# BreakoutBoard.net
KiCad netlist of a schematic drawn in EAGLE
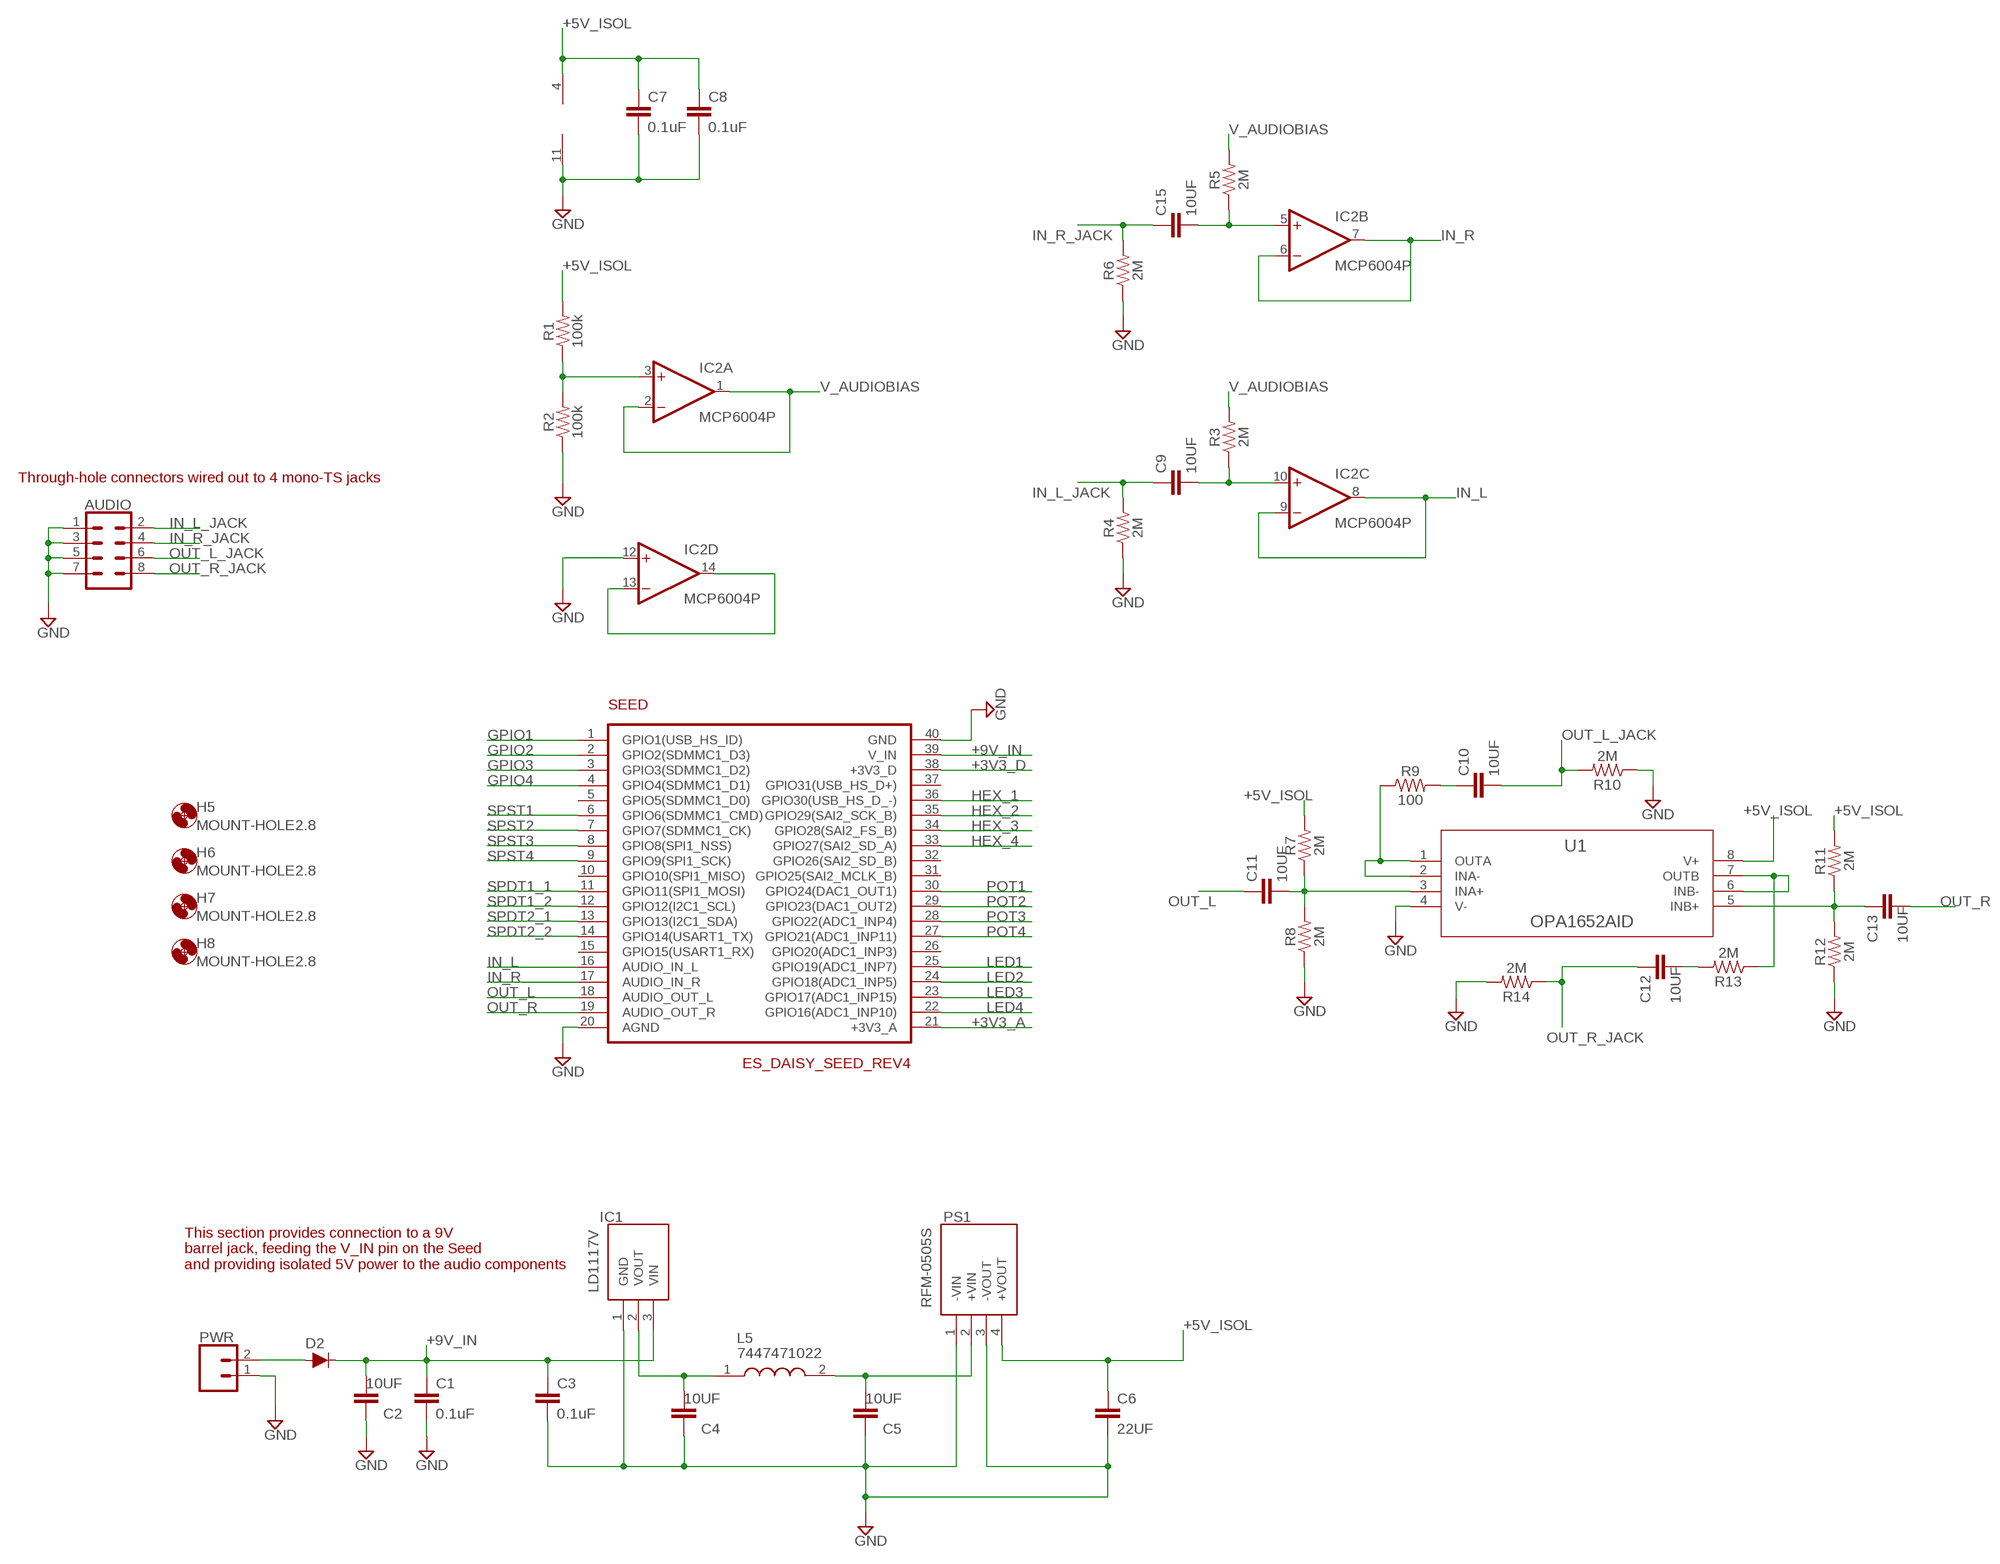
[diagram p0: schematic, sheet 1]
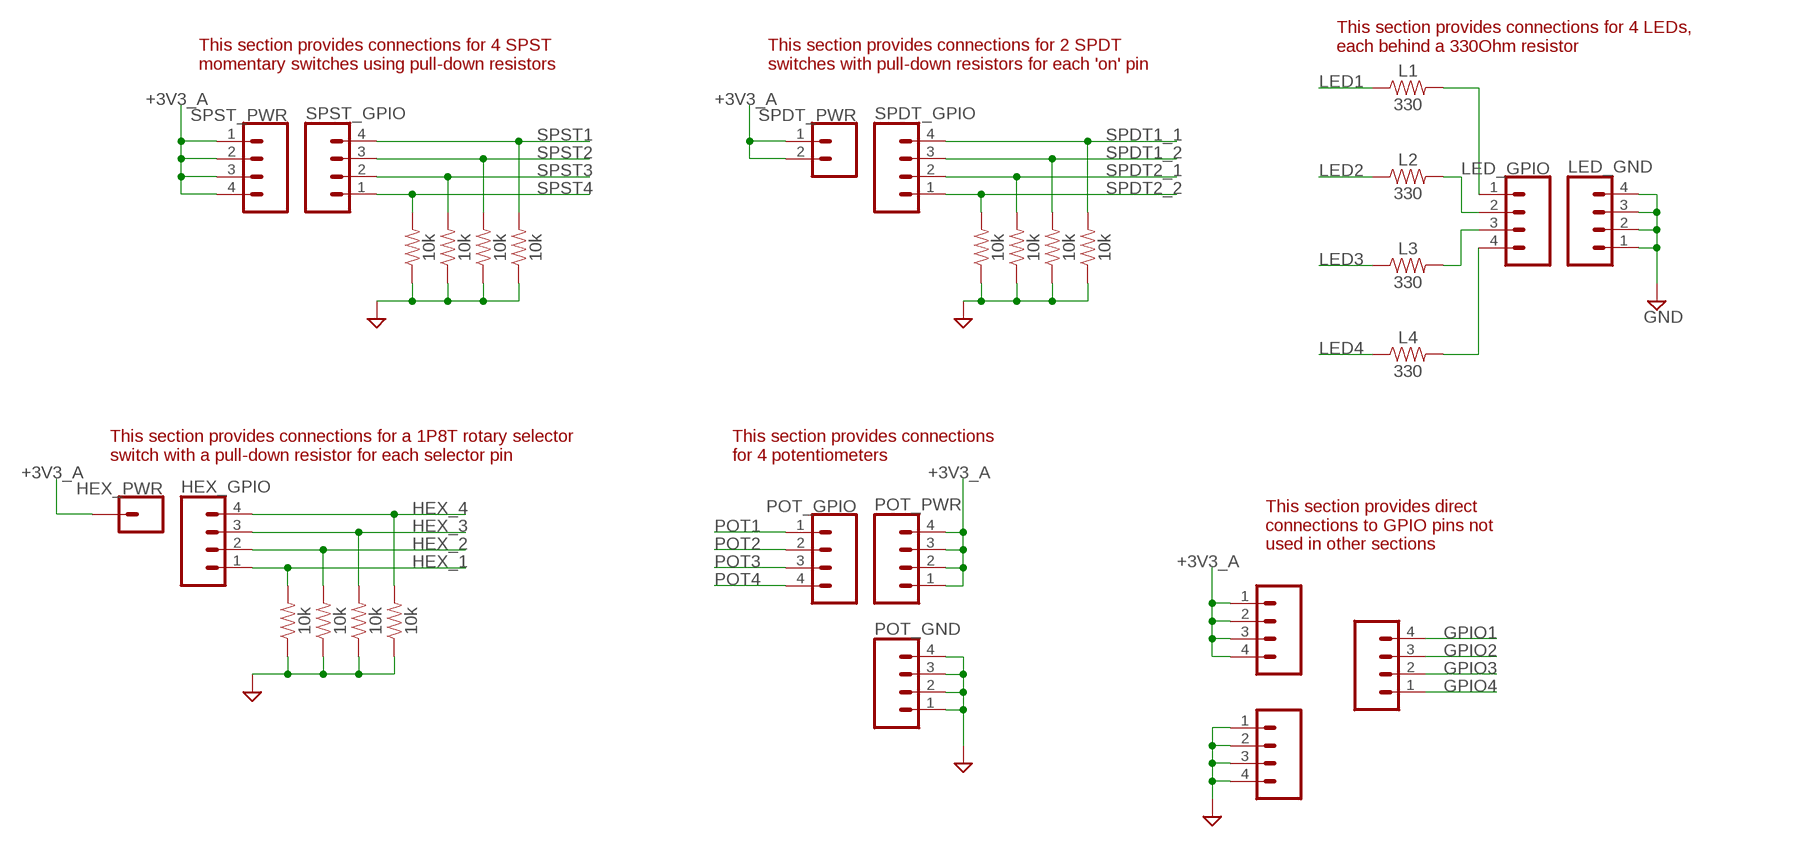
[diagram p1: schematic, sheet 2]

(export (version "E")
  (design (tool "Eeschema 10.0.6"))
  (components
    (comp (ref "EX_GND")
      (value "CONN_04")
      (footprint "eagle-import:1X04")
      (libsource (lib "eagle-import") (part "CONN_04"))
    )
    (comp (ref "EX_GPIOS")
      (value "CONN_04")
      (footprint "eagle-import:1X04")
      (libsource (lib "eagle-import") (part "CONN_04"))
    )
    (comp (ref "EX_PWR")
      (value "CONN_04")
      (footprint "eagle-import:1X04")
      (libsource (lib "eagle-import") (part "CONN_04"))
    )
    (comp (ref "HEX_GPIO")
      (value "CONN_04")
      (footprint "eagle-import:1X04")
      (libsource (lib "eagle-import") (part "CONN_04"))
    )
    (comp (ref "HEX_PWR")
      (value "CONN_01")
      (footprint "eagle-import:1X01")
      (libsource (lib "eagle-import") (part "CONN_01"))
    )
    (comp (ref "L1")
      (value "330")
      (footprint "eagle-import:AXIAL-0.3")
      (libsource (lib "eagle-import") (part "330OHM-HORIZ-1/10W-5%"))
    )
    (comp (ref "L2")
      (value "330")
      (footprint "eagle-import:AXIAL-0.3")
      (libsource (lib "eagle-import") (part "330OHM-HORIZ-1/10W-5%"))
    )
    (comp (ref "L3")
      (value "330")
      (footprint "eagle-import:AXIAL-0.3")
      (libsource (lib "eagle-import") (part "330OHM-HORIZ-1/10W-5%"))
    )
    (comp (ref "L4")
      (value "330")
      (footprint "eagle-import:AXIAL-0.3")
      (libsource (lib "eagle-import") (part "330OHM-HORIZ-1/10W-5%"))
    )
    (comp (ref "LED_GND")
      (value "CONN_04")
      (footprint "eagle-import:1X04")
      (libsource (lib "eagle-import") (part "CONN_04"))
    )
    (comp (ref "LED_GPIO")
      (value "CONN_04")
      (footprint "eagle-import:1X04")
      (libsource (lib "eagle-import") (part "CONN_04"))
    )
    (comp (ref "POT_GND")
      (value "CONN_04")
      (footprint "eagle-import:1X04")
      (libsource (lib "eagle-import") (part "CONN_04"))
    )
    (comp (ref "POT_GPIO")
      (value "CONN_04")
      (footprint "eagle-import:1X04")
      (libsource (lib "eagle-import") (part "CONN_04"))
    )
    (comp (ref "POT_PWR")
      (value "CONN_04")
      (footprint "eagle-import:1X04")
      (libsource (lib "eagle-import") (part "CONN_04"))
    )
    (comp (ref "R15")
      (value "10k")
      (footprint "eagle-import:AXIAL-0.3")
      (libsource (lib "eagle-import") (part "10KOHM-HORIZ-1/4W-5%"))
    )
    (comp (ref "R16")
      (value "10k")
      (footprint "eagle-import:AXIAL-0.3")
      (libsource (lib "eagle-import") (part "10KOHM-HORIZ-1/4W-5%"))
    )
    (comp (ref "R17")
      (value "10k")
      (footprint "eagle-import:AXIAL-0.3")
      (libsource (lib "eagle-import") (part "10KOHM-HORIZ-1/4W-5%"))
    )
    (comp (ref "R18")
      (value "10k")
      (footprint "eagle-import:AXIAL-0.3")
      (libsource (lib "eagle-import") (part "10KOHM-HORIZ-1/4W-5%"))
    )
    (comp (ref "R19")
      (value "10k")
      (footprint "eagle-import:AXIAL-0.3")
      (libsource (lib "eagle-import") (part "10KOHM-HORIZ-1/4W-5%"))
    )
    (comp (ref "R20")
      (value "10k")
      (footprint "eagle-import:AXIAL-0.3")
      (libsource (lib "eagle-import") (part "10KOHM-HORIZ-1/4W-5%"))
    )
    (comp (ref "R21")
      (value "10k")
      (footprint "eagle-import:AXIAL-0.3")
      (libsource (lib "eagle-import") (part "10KOHM-HORIZ-1/4W-5%"))
    )
    (comp (ref "R22")
      (value "10k")
      (footprint "eagle-import:AXIAL-0.3")
      (libsource (lib "eagle-import") (part "10KOHM-HORIZ-1/4W-5%"))
    )
    (comp (ref "R23")
      (value "10k")
      (footprint "eagle-import:AXIAL-0.3")
      (libsource (lib "eagle-import") (part "10KOHM-HORIZ-1/4W-5%"))
    )
    (comp (ref "R24")
      (value "10k")
      (footprint "eagle-import:AXIAL-0.3")
      (libsource (lib "eagle-import") (part "10KOHM-HORIZ-1/4W-5%"))
    )
    (comp (ref "R25")
      (value "10k")
      (footprint "eagle-import:AXIAL-0.3")
      (libsource (lib "eagle-import") (part "10KOHM-HORIZ-1/4W-5%"))
    )
    (comp (ref "R26")
      (value "10k")
      (footprint "eagle-import:AXIAL-0.3")
      (libsource (lib "eagle-import") (part "10KOHM-HORIZ-1/4W-5%"))
    )
    (comp (ref "SPDT_GPIO")
      (value "CONN_04")
      (footprint "eagle-import:1X04")
      (libsource (lib "eagle-import") (part "CONN_04"))
    )
    (comp (ref "SPDT_PWR")
      (value "CONN_02")
      (footprint "eagle-import:1X02")
      (libsource (lib "eagle-import") (part "CONN_02"))
    )
    (comp (ref "SPST_GPIO")
      (value "CONN_04")
      (footprint "eagle-import:1X04")
      (libsource (lib "eagle-import") (part "CONN_04"))
    )
    (comp (ref "SPST_PWR")
      (value "CONN_04")
      (footprint "eagle-import:1X04")
      (libsource (lib "eagle-import") (part "CONN_04"))
    )
    (comp (ref "AUDIO")
      (value "CONN_04X2")
      (footprint "eagle-import:2X4")
      (libsource (lib "eagle-import") (part "CONN_04X2"))
    )
    (comp (ref "C1")
      (value "0.1uF")
      (footprint "eagle-import:CAP-PTH-SMALL-KIT")
      (libsource (lib "eagle-import") (part "0.1UF-KIT-EZ-50V-20%"))
    )
    (comp (ref "C2")
      (value "10UF")
      (footprint "eagle-import:CAP-PTH-SMALL-KIT")
      (libsource (lib "eagle-import") (part "10UF"))
    )
    (comp (ref "C3")
      (value "0.1uF")
      (footprint "eagle-import:CAP-PTH-SMALL-KIT")
      (libsource (lib "eagle-import") (part "0.1UF-KIT-EZ-50V-20%"))
    )
    (comp (ref "C4")
      (value "10UF")
      (footprint "eagle-import:CAP-PTH-SMALL-KIT")
      (libsource (lib "eagle-import") (part "10UF"))
    )
    (comp (ref "C5")
      (value "10UF")
      (footprint "eagle-import:CAP-PTH-SMALL-KIT")
      (libsource (lib "eagle-import") (part "10UF"))
    )
    (comp (ref "C6")
      (value "22UF")
      (footprint "eagle-import:CAP-PTH-SMALL-KIT")
      (libsource (lib "eagle-import") (part "22UF"))
    )
    (comp (ref "C7")
      (value "0.1uF")
      (footprint "eagle-import:CAP-PTH-SMALL-KIT")
      (libsource (lib "eagle-import") (part "0.1UF-KIT-EZ-50V-20%"))
    )
    (comp (ref "C8")
      (value "0.1uF")
      (footprint "eagle-import:CAP-PTH-SMALL-KIT")
      (libsource (lib "eagle-import") (part "0.1UF-KIT-EZ-50V-20%"))
    )
    (comp (ref "C9")
      (value "10UF")
      (footprint "eagle-import:CAP-PTH-SMALL-KIT")
      (libsource (lib "eagle-import") (part "10UF"))
    )
    (comp (ref "C10")
      (value "10UF")
      (footprint "eagle-import:CAP-PTH-SMALL-KIT")
      (libsource (lib "eagle-import") (part "10UF"))
    )
    (comp (ref "C11")
      (value "10UF")
      (footprint "eagle-import:CAP-PTH-SMALL-KIT")
      (libsource (lib "eagle-import") (part "10UF"))
    )
    (comp (ref "C12")
      (value "10UF")
      (footprint "eagle-import:CAP-PTH-SMALL-KIT")
      (libsource (lib "eagle-import") (part "10UF"))
    )
    (comp (ref "C13")
      (value "10UF")
      (footprint "eagle-import:CAP-PTH-SMALL-KIT")
      (libsource (lib "eagle-import") (part "10UF"))
    )
    (comp (ref "C15")
      (value "10UF")
      (footprint "eagle-import:CAP-PTH-SMALL-KIT")
      (libsource (lib "eagle-import") (part "10UF"))
    )
    (comp (ref "D2")
      (value "200mA/100V/1V")
      (footprint "eagle-import:DIODE-1N4148")
      (libsource (lib "eagle-import") (part "DIODE-1N4148"))
    )
    (comp (ref "H5")
      (value "MOUNT-HOLE2.8")
      (footprint "eagle-import:2,8")
      (libsource (lib "eagle-import") (part "MOUNT-HOLE2.8"))
    )
    (comp (ref "H6")
      (value "MOUNT-HOLE2.8")
      (footprint "eagle-import:2,8")
      (libsource (lib "eagle-import") (part "MOUNT-HOLE2.8"))
    )
    (comp (ref "H7")
      (value "MOUNT-HOLE2.8")
      (footprint "eagle-import:2,8")
      (libsource (lib "eagle-import") (part "MOUNT-HOLE2.8"))
    )
    (comp (ref "H8")
      (value "MOUNT-HOLE2.8")
      (footprint "eagle-import:2,8")
      (libsource (lib "eagle-import") (part "MOUNT-HOLE2.8"))
    )
    (comp (ref "IC1")
      (value "LD1117V")
      (footprint "eagle-import:TO255P460X1020X2008-3P")
      (fields (field (name "MOUSER_PART_NUMBER") "511-LD1117V"))
      (libsource (lib "eagle-import") (part "LD1117V"))
    )
    (comp (ref "IC2")
      (value "MCP6004P")
      (footprint "eagle-import:DIL14")
      (libsource (lib "eagle-import") (part "MCP6004P"))
    )
    (comp (ref "L5")
      (value "7447471022")
      (footprint "eagle-import:WE-TIS_111190")
      (fields (field (name "MOUSER_PART_NUMBER") "710-7447471022"))
      (libsource (lib "eagle-import") (part "7447471022"))
    )
    (comp (ref "PS1")
      (value "RFM-0505S")
      (footprint "eagle-import:RFM0505S")
      (fields (field (name "MOUSER_PART_NUMBER") "919-RFM-0505S"))
      (libsource (lib "eagle-import") (part "RFM-0505S"))
    )
    (comp (ref "PWR")
      (value "CONN_02")
      (footprint "eagle-import:1X02")
      (libsource (lib "eagle-import") (part "CONN_02"))
    )
    (comp (ref "R1")
      (value "100k")
      (footprint "eagle-import:AXIAL-0.3")
      (libsource (lib "eagle-import") (part "100KOHM-HORIZ-1/4W-5%"))
    )
    (comp (ref "R2")
      (value "100k")
      (footprint "eagle-import:AXIAL-0.3")
      (libsource (lib "eagle-import") (part "100KOHM-HORIZ-1/4W-5%"))
    )
    (comp (ref "R3")
      (value "2M")
      (footprint "eagle-import:AXIAL-0.3")
      (libsource (lib "eagle-import") (part "2MOHM-HORIZ-1/4W-5%"))
    )
    (comp (ref "R4")
      (value "2M")
      (footprint "eagle-import:AXIAL-0.3")
      (libsource (lib "eagle-import") (part "2MOHM-HORIZ-1/4W-5%"))
    )
    (comp (ref "R5")
      (value "2M")
      (footprint "eagle-import:AXIAL-0.3")
      (libsource (lib "eagle-import") (part "2MOHM-HORIZ-1/4W-5%"))
    )
    (comp (ref "R6")
      (value "2M")
      (footprint "eagle-import:AXIAL-0.3")
      (libsource (lib "eagle-import") (part "2MOHM-HORIZ-1/4W-5%"))
    )
    (comp (ref "R7")
      (value "2M")
      (footprint "eagle-import:AXIAL-0.3")
      (libsource (lib "eagle-import") (part "2MOHM-HORIZ-1/4W-5%"))
    )
    (comp (ref "R8")
      (value "2M")
      (footprint "eagle-import:AXIAL-0.3")
      (libsource (lib "eagle-import") (part "2MOHM-HORIZ-1/4W-5%"))
    )
    (comp (ref "R9")
      (value "100")
      (footprint "eagle-import:AXIAL-0.3")
      (libsource (lib "eagle-import") (part "100OHM-HORIZ-1/4W-1%"))
    )
    (comp (ref "R10")
      (value "2M")
      (footprint "eagle-import:AXIAL-0.3")
      (libsource (lib "eagle-import") (part "2MOHM-HORIZ-1/4W-5%"))
    )
    (comp (ref "R11")
      (value "2M")
      (footprint "eagle-import:AXIAL-0.3")
      (libsource (lib "eagle-import") (part "2MOHM-HORIZ-1/4W-5%"))
    )
    (comp (ref "R12")
      (value "2M")
      (footprint "eagle-import:AXIAL-0.3")
      (libsource (lib "eagle-import") (part "2MOHM-HORIZ-1/4W-5%"))
    )
    (comp (ref "R13")
      (value "2M")
      (footprint "eagle-import:AXIAL-0.3")
      (libsource (lib "eagle-import") (part "2MOHM-HORIZ-1/4W-5%"))
    )
    (comp (ref "R14")
      (value "2M")
      (footprint "eagle-import:AXIAL-0.3")
      (libsource (lib "eagle-import") (part "2MOHM-HORIZ-1/4W-5%"))
    )
    (comp (ref "SEED")
      (value "ES_DAISY_SEED_REV4")
      (footprint "eagle-import:ES_DAISY_SEED")
      (libsource (lib "eagle-import") (part "ES_DAISY_SEED_REV4"))
    )
    (comp (ref "U1")
      (value "OPA1652AID")
      (footprint "eagle-import:D8")
      (fields
        (field (name "GENERIC_PART_NUMBER") "OPA1652")
        (field (name "MANUFACTURER") "Texas Instruments")
      )
      (libsource (lib "eagle-import") (part "OPA1652AID"))
    )
  )
  (nets
    (net (code "1") (name "+3V3_A") (class "Default")
      (node (ref "EX_PWR") (pin "1") (pinfunction "1_1") (pintype "passive"))
      (node (ref "EX_PWR") (pin "2") (pinfunction "2_2") (pintype "passive"))
      (node (ref "EX_PWR") (pin "3") (pinfunction "3_3") (pintype "passive"))
      (node (ref "EX_PWR") (pin "4") (pinfunction "4_4") (pintype "passive"))
      (node (ref "HEX_PWR") (pin "1") (pinfunction "1_1") (pintype "passive"))
      (node (ref "POT_PWR") (pin "1") (pinfunction "1_1") (pintype "passive"))
      (node (ref "POT_PWR") (pin "2") (pinfunction "2_2") (pintype "passive"))
      (node (ref "POT_PWR") (pin "3") (pinfunction "3_3") (pintype "passive"))
      (node (ref "POT_PWR") (pin "4") (pinfunction "4_4") (pintype "passive"))
      (node (ref "SEED") (pin "21") (pinfunction "+3V3_A_21") (pintype "bidirectional"))
      (node (ref "SPDT_PWR") (pin "1") (pinfunction "1_1") (pintype "passive"))
      (node (ref "SPDT_PWR") (pin "2") (pinfunction "2_2") (pintype "passive"))
      (node (ref "SPST_PWR") (pin "1") (pinfunction "1_1") (pintype "passive"))
      (node (ref "SPST_PWR") (pin "2") (pinfunction "2_2") (pintype "passive"))
      (node (ref "SPST_PWR") (pin "3") (pinfunction "3_3") (pintype "passive"))
      (node (ref "SPST_PWR") (pin "4") (pinfunction "4_4") (pintype "passive"))
    )
    (net (code "2") (name "+3V3_D") (class "Default")
      (node (ref "SEED") (pin "38") (pinfunction "+3V3_D_38") (pintype "bidirectional"))
    )
    (net (code "3") (name "+5V_ISOL") (class "Default")
      (node (ref "C6") (pin "1") (pinfunction "1_1") (pintype "passive"))
      (node (ref "C7") (pin "1") (pinfunction "1_1") (pintype "passive"))
      (node (ref "C8") (pin "1") (pinfunction "1_1") (pintype "passive"))
      (node (ref "IC2") (pin "4") (pinfunction "V+_4") (pintype "power_in"))
      (node (ref "PS1") (pin "4") (pinfunction "+VOUT_4") (pintype "bidirectional"))
      (node (ref "R1") (pin "P$2") (pinfunction "2_P$2") (pintype "passive"))
      (node (ref "R11") (pin "P$2") (pinfunction "2_P$2") (pintype "passive"))
      (node (ref "R7") (pin "P$2") (pinfunction "2_P$2") (pintype "passive"))
      (node (ref "U1") (pin "8") (pinfunction "V+_8") (pintype "power_in"))
    )
    (net (code "4") (name "+9V_IN") (class "Default")
      (node (ref "C1") (pin "1") (pinfunction "1_1") (pintype "passive"))
      (node (ref "C2") (pin "2") (pinfunction "2_2") (pintype "passive"))
      (node (ref "C3") (pin "1") (pinfunction "1_1") (pintype "passive"))
      (node (ref "D2") (pin "C") (pinfunction "C_C") (pintype "passive"))
      (node (ref "IC1") (pin "3") (pinfunction "VIN_3") (pintype "bidirectional"))
      (node (ref "SEED") (pin "39") (pinfunction "V_IN_39") (pintype "bidirectional"))
    )
    (net (code "5") (name "GND") (class "Default")
      (node (ref "AUDIO") (pin "1") (pinfunction "1_1") (pintype "passive"))
      (node (ref "AUDIO") (pin "3") (pinfunction "3_3") (pintype "passive"))
      (node (ref "AUDIO") (pin "5") (pinfunction "5_5") (pintype "passive"))
      (node (ref "AUDIO") (pin "7") (pinfunction "7_7") (pintype "passive"))
      (node (ref "C1") (pin "2") (pinfunction "2_2") (pintype "passive"))
      (node (ref "C2") (pin "1") (pinfunction "1_1") (pintype "passive"))
      (node (ref "C3") (pin "2") (pinfunction "2_2") (pintype "passive"))
      (node (ref "C4") (pin "1") (pinfunction "1_1") (pintype "passive"))
      (node (ref "C5") (pin "1") (pinfunction "1_1") (pintype "passive"))
      (node (ref "C6") (pin "2") (pinfunction "2_2") (pintype "passive"))
      (node (ref "C7") (pin "2") (pinfunction "2_2") (pintype "passive"))
      (node (ref "C8") (pin "2") (pinfunction "2_2") (pintype "passive"))
      (node (ref "EX_GND") (pin "1") (pinfunction "1_1") (pintype "passive"))
      (node (ref "EX_GND") (pin "2") (pinfunction "2_2") (pintype "passive"))
      (node (ref "EX_GND") (pin "3") (pinfunction "3_3") (pintype "passive"))
      (node (ref "EX_GND") (pin "4") (pinfunction "4_4") (pintype "passive"))
      (node (ref "IC1") (pin "1") (pinfunction "GND_1") (pintype "bidirectional"))
      (node (ref "IC2") (pin "11") (pinfunction "V-_11") (pintype "power_in"))
      (node (ref "IC2") (pin "12") (pinfunction "+IN_12") (pintype "input"))
      (node (ref "LED_GND") (pin "1") (pinfunction "1_1") (pintype "passive"))
      (node (ref "LED_GND") (pin "2") (pinfunction "2_2") (pintype "passive"))
      (node (ref "LED_GND") (pin "3") (pinfunction "3_3") (pintype "passive"))
      (node (ref "LED_GND") (pin "4") (pinfunction "4_4") (pintype "passive"))
      (node (ref "POT_GND") (pin "1") (pinfunction "1_1") (pintype "passive"))
      (node (ref "POT_GND") (pin "2") (pinfunction "2_2") (pintype "passive"))
      (node (ref "POT_GND") (pin "3") (pinfunction "3_3") (pintype "passive"))
      (node (ref "POT_GND") (pin "4") (pinfunction "4_4") (pintype "passive"))
      (node (ref "PS1") (pin "1") (pinfunction "-VIN_1") (pintype "bidirectional"))
      (node (ref "PS1") (pin "3") (pinfunction "-VOUT_3") (pintype "bidirectional"))
      (node (ref "PWR") (pin "1") (pinfunction "1_1") (pintype "passive"))
      (node (ref "R10") (pin "P$1") (pinfunction "1_P$1") (pintype "passive"))
      (node (ref "R12") (pin "P$1") (pinfunction "1_P$1") (pintype "passive"))
      (node (ref "R14") (pin "P$2") (pinfunction "2_P$2") (pintype "passive"))
      (node (ref "R15") (pin "P$1") (pinfunction "1_P$1") (pintype "passive"))
      (node (ref "R16") (pin "P$1") (pinfunction "1_P$1") (pintype "passive"))
      (node (ref "R17") (pin "P$1") (pinfunction "1_P$1") (pintype "passive"))
      (node (ref "R18") (pin "P$1") (pinfunction "1_P$1") (pintype "passive"))
      (node (ref "R19") (pin "P$1") (pinfunction "1_P$1") (pintype "passive"))
      (node (ref "R2") (pin "P$1") (pinfunction "1_P$1") (pintype "passive"))
      (node (ref "R20") (pin "P$1") (pinfunction "1_P$1") (pintype "passive"))
      (node (ref "R21") (pin "P$1") (pinfunction "1_P$1") (pintype "passive"))
      (node (ref "R22") (pin "P$1") (pinfunction "1_P$1") (pintype "passive"))
      (node (ref "R23") (pin "P$1") (pinfunction "1_P$1") (pintype "passive"))
      (node (ref "R24") (pin "P$1") (pinfunction "1_P$1") (pintype "passive"))
      (node (ref "R25") (pin "P$1") (pinfunction "1_P$1") (pintype "passive"))
      (node (ref "R26") (pin "P$1") (pinfunction "1_P$1") (pintype "passive"))
      (node (ref "R4") (pin "P$1") (pinfunction "1_P$1") (pintype "passive"))
      (node (ref "R6") (pin "P$1") (pinfunction "1_P$1") (pintype "passive"))
      (node (ref "R8") (pin "P$1") (pinfunction "1_P$1") (pintype "passive"))
      (node (ref "SEED") (pin "20") (pinfunction "AGND_20") (pintype "bidirectional"))
      (node (ref "SEED") (pin "40") (pinfunction "GND_40") (pintype "bidirectional"))
      (node (ref "U1") (pin "4") (pinfunction "V-_4") (pintype "power_in"))
    )
    (net (code "6") (name "GPIO1") (class "Default")
      (node (ref "EX_GPIOS") (pin "4") (pinfunction "4_4") (pintype "passive"))
      (node (ref "SEED") (pin "1") (pinfunction "GPIO1(USB_HS_ID)_1") (pintype "bidirectional"))
    )
    (net (code "7") (name "GPIO2") (class "Default")
      (node (ref "EX_GPIOS") (pin "3") (pinfunction "3_3") (pintype "passive"))
      (node (ref "SEED") (pin "2") (pinfunction "GPIO2(SDMMC1_D3)_2") (pintype "bidirectional"))
    )
    (net (code "8") (name "GPIO3") (class "Default")
      (node (ref "EX_GPIOS") (pin "2") (pinfunction "2_2") (pintype "passive"))
      (node (ref "SEED") (pin "3") (pinfunction "GPIO3(SDMMC1_D2)_3") (pintype "bidirectional"))
    )
    (net (code "9") (name "GPIO4") (class "Default")
      (node (ref "EX_GPIOS") (pin "1") (pinfunction "1_1") (pintype "passive"))
      (node (ref "SEED") (pin "4") (pinfunction "GPIO4(SDMMC1_D1)_4") (pintype "bidirectional"))
    )
    (net (code "10") (name "HEX_1") (class "Default")
      (node (ref "HEX_GPIO") (pin "1") (pinfunction "1_1") (pintype "passive"))
      (node (ref "R23") (pin "P$2") (pinfunction "2_P$2") (pintype "passive"))
      (node (ref "SEED") (pin "36") (pinfunction "GPIO30(USB_HS_D_-)_36") (pintype "bidirectional"))
    )
    (net (code "11") (name "HEX_2") (class "Default")
      (node (ref "HEX_GPIO") (pin "2") (pinfunction "2_2") (pintype "passive"))
      (node (ref "R24") (pin "P$2") (pinfunction "2_P$2") (pintype "passive"))
      (node (ref "SEED") (pin "35") (pinfunction "GPIO29(SAI2_SCK_B)_35") (pintype "bidirectional"))
    )
    (net (code "12") (name "HEX_3") (class "Default")
      (node (ref "HEX_GPIO") (pin "3") (pinfunction "3_3") (pintype "passive"))
      (node (ref "R25") (pin "P$2") (pinfunction "2_P$2") (pintype "passive"))
      (node (ref "SEED") (pin "34") (pinfunction "GPIO28(SAI2_FS_B)_34") (pintype "bidirectional"))
    )
    (net (code "13") (name "HEX_4") (class "Default")
      (node (ref "HEX_GPIO") (pin "4") (pinfunction "4_4") (pintype "passive"))
      (node (ref "R26") (pin "P$2") (pinfunction "2_P$2") (pintype "passive"))
      (node (ref "SEED") (pin "33") (pinfunction "GPIO27(SAI2_SD_A)_33") (pintype "bidirectional"))
    )
    (net (code "14") (name "IN_L") (class "Default")
      (node (ref "IC2") (pin "8") (pinfunction "OUT_8") (pintype "output"))
      (node (ref "IC2") (pin "9") (pinfunction "-IN_9") (pintype "input"))
      (node (ref "SEED") (pin "16") (pinfunction "AUDIO_IN_L_16") (pintype "bidirectional"))
    )
    (net (code "15") (name "IN_L_JACK") (class "Default")
      (node (ref "AUDIO") (pin "2") (pinfunction "2_2") (pintype "passive"))
      (node (ref "C9") (pin "1") (pinfunction "1_1") (pintype "passive"))
      (node (ref "R4") (pin "P$2") (pinfunction "2_P$2") (pintype "passive"))
    )
    (net (code "16") (name "IN_R") (class "Default")
      (node (ref "IC2") (pin "6") (pinfunction "-IN_6") (pintype "input"))
      (node (ref "IC2") (pin "7") (pinfunction "OUT_7") (pintype "output"))
      (node (ref "SEED") (pin "17") (pinfunction "AUDIO_IN_R_17") (pintype "bidirectional"))
    )
    (net (code "17") (name "IN_R_JACK") (class "Default")
      (node (ref "AUDIO") (pin "4") (pinfunction "4_4") (pintype "passive"))
      (node (ref "C15") (pin "1") (pinfunction "1_1") (pintype "passive"))
      (node (ref "R6") (pin "P$2") (pinfunction "2_P$2") (pintype "passive"))
    )
    (net (code "18") (name "LED1") (class "Default")
      (node (ref "L1") (pin "P$1") (pinfunction "1_P$1") (pintype "passive"))
      (node (ref "SEED") (pin "25") (pinfunction "GPIO19(ADC1_INP7)_25") (pintype "bidirectional"))
    )
    (net (code "19") (name "LED2") (class "Default")
      (node (ref "L2") (pin "P$1") (pinfunction "1_P$1") (pintype "passive"))
      (node (ref "SEED") (pin "24") (pinfunction "GPIO18(ADC1_INP5)_24") (pintype "bidirectional"))
    )
    (net (code "20") (name "LED3") (class "Default")
      (node (ref "L3") (pin "P$1") (pinfunction "1_P$1") (pintype "passive"))
      (node (ref "SEED") (pin "23") (pinfunction "GPIO17(ADC1_INP15)_23") (pintype "bidirectional"))
    )
    (net (code "21") (name "LED4") (class "Default")
      (node (ref "L4") (pin "P$1") (pinfunction "1_P$1") (pintype "passive"))
      (node (ref "SEED") (pin "22") (pinfunction "GPIO16(ADC1_INP10)_22") (pintype "bidirectional"))
    )
    (net (code "22") (name "Net-(D2-PadA)") (class "Default")
      (node (ref "D2") (pin "A") (pinfunction "A_A") (pintype "passive"))
      (node (ref "PWR") (pin "2") (pinfunction "2_2") (pintype "passive"))
    )
    (net (code "23") (name "Net-(IC1-VOUT)") (class "Default")
      (node (ref "C4") (pin "2") (pinfunction "2_2") (pintype "passive"))
      (node (ref "IC1") (pin "2") (pinfunction "VOUT_2") (pintype "bidirectional"))
      (node (ref "L5") (pin "1") (pinfunction "1_1") (pintype "bidirectional"))
    )
    (net (code "24") (name "Net-(IC2A-+IN)") (class "Default")
      (node (ref "IC2") (pin "3") (pinfunction "+IN_3") (pintype "input"))
      (node (ref "R1") (pin "P$1") (pinfunction "1_P$1") (pintype "passive"))
      (node (ref "R2") (pin "P$2") (pinfunction "2_P$2") (pintype "passive"))
    )
    (net (code "25") (name "Net-(IC2B-+IN)") (class "Default")
      (node (ref "C15") (pin "2") (pinfunction "2_2") (pintype "passive"))
      (node (ref "IC2") (pin "5") (pinfunction "+IN_5") (pintype "input"))
      (node (ref "R5") (pin "P$1") (pinfunction "1_P$1") (pintype "passive"))
    )
    (net (code "26") (name "Net-(IC2C-+IN)") (class "Default")
      (node (ref "C9") (pin "2") (pinfunction "2_2") (pintype "passive"))
      (node (ref "IC2") (pin "10") (pinfunction "+IN_10") (pintype "input"))
      (node (ref "R3") (pin "P$1") (pinfunction "1_P$1") (pintype "passive"))
    )
    (net (code "27") (name "Net-(IC2D--IN)") (class "Default")
      (node (ref "IC2") (pin "13") (pinfunction "-IN_13") (pintype "input"))
      (node (ref "IC2") (pin "14") (pinfunction "OUT_14") (pintype "output"))
    )
    (net (code "28") (name "Net-(L1-2)") (class "Default")
      (node (ref "L1") (pin "P$2") (pinfunction "2_P$2") (pintype "passive"))
      (node (ref "LED_GPIO") (pin "1") (pinfunction "1_1") (pintype "passive"))
    )
    (net (code "29") (name "Net-(L2-2)") (class "Default")
      (node (ref "L2") (pin "P$2") (pinfunction "2_P$2") (pintype "passive"))
      (node (ref "LED_GPIO") (pin "2") (pinfunction "2_2") (pintype "passive"))
    )
    (net (code "30") (name "Net-(L3-2)") (class "Default")
      (node (ref "L3") (pin "P$2") (pinfunction "2_P$2") (pintype "passive"))
      (node (ref "LED_GPIO") (pin "3") (pinfunction "3_3") (pintype "passive"))
    )
    (net (code "31") (name "Net-(L4-2)") (class "Default")
      (node (ref "L4") (pin "P$2") (pinfunction "2_P$2") (pintype "passive"))
      (node (ref "LED_GPIO") (pin "4") (pinfunction "4_4") (pintype "passive"))
    )
    (net (code "32") (name "Net-(PS1-+VIN)") (class "Default")
      (node (ref "C5") (pin "2") (pinfunction "2_2") (pintype "passive"))
      (node (ref "L5") (pin "2") (pinfunction "2_2") (pintype "bidirectional"))
      (node (ref "PS1") (pin "2") (pinfunction "+VIN_2") (pintype "bidirectional"))
    )
    (net (code "33") (name "Net-(R7-1)") (class "Default")
      (node (ref "C11") (pin "2") (pinfunction "2_2") (pintype "passive"))
      (node (ref "R7") (pin "P$1") (pinfunction "1_P$1") (pintype "passive"))
      (node (ref "R8") (pin "P$2") (pinfunction "2_P$2") (pintype "passive"))
      (node (ref "U1") (pin "3") (pinfunction "INA+_3") (pintype "input"))
    )
    (net (code "34") (name "Net-(R9-1)") (class "Default")
      (node (ref "R9") (pin "P$1") (pinfunction "1_P$1") (pintype "passive"))
      (node (ref "U1") (pin "1") (pinfunction "OUTA_1") (pintype "output"))
      (node (ref "U1") (pin "2") (pinfunction "INA-_2") (pintype "input"))
    )
    (net (code "35") (name "Net-(R9-2)") (class "Default")
      (node (ref "C10") (pin "1") (pinfunction "1_1") (pintype "passive"))
      (node (ref "R9") (pin "P$2") (pinfunction "2_P$2") (pintype "passive"))
    )
    (net (code "36") (name "Net-(R11-1)") (class "Default")
      (node (ref "C13") (pin "1") (pinfunction "1_1") (pintype "passive"))
      (node (ref "R11") (pin "P$1") (pinfunction "1_P$1") (pintype "passive"))
      (node (ref "R12") (pin "P$2") (pinfunction "2_P$2") (pintype "passive"))
      (node (ref "U1") (pin "5") (pinfunction "INB+_5") (pintype "input"))
    )
    (net (code "37") (name "Net-(R13-1)") (class "Default")
      (node (ref "R13") (pin "P$1") (pinfunction "1_P$1") (pintype "passive"))
      (node (ref "U1") (pin "6") (pinfunction "INB-_6") (pintype "input"))
      (node (ref "U1") (pin "7") (pinfunction "OUTB_7") (pintype "output"))
    )
    (net (code "38") (name "Net-(R13-2)") (class "Default")
      (node (ref "C12") (pin "2") (pinfunction "2_2") (pintype "passive"))
      (node (ref "R13") (pin "P$2") (pinfunction "2_P$2") (pintype "passive"))
    )
    (net (code "39") (name "OUT_L") (class "Default")
      (node (ref "C11") (pin "1") (pinfunction "1_1") (pintype "passive"))
      (node (ref "SEED") (pin "18") (pinfunction "AUDIO_OUT_L_18") (pintype "bidirectional"))
    )
    (net (code "40") (name "OUT_L_JACK") (class "Default")
      (node (ref "AUDIO") (pin "6") (pinfunction "6_6") (pintype "passive"))
      (node (ref "C10") (pin "2") (pinfunction "2_2") (pintype "passive"))
      (node (ref "R10") (pin "P$2") (pinfunction "2_P$2") (pintype "passive"))
    )
    (net (code "41") (name "OUT_R") (class "Default")
      (node (ref "C13") (pin "2") (pinfunction "2_2") (pintype "passive"))
      (node (ref "SEED") (pin "19") (pinfunction "AUDIO_OUT_R_19") (pintype "bidirectional"))
    )
    (net (code "42") (name "OUT_R_JACK") (class "Default")
      (node (ref "AUDIO") (pin "8") (pinfunction "8_8") (pintype "passive"))
      (node (ref "C12") (pin "1") (pinfunction "1_1") (pintype "passive"))
      (node (ref "R14") (pin "P$1") (pinfunction "1_P$1") (pintype "passive"))
    )
    (net (code "43") (name "POT1") (class "Default")
      (node (ref "POT_GPIO") (pin "1") (pinfunction "1_1") (pintype "passive"))
      (node (ref "SEED") (pin "30") (pinfunction "GPIO24(DAC1_OUT1)_30") (pintype "bidirectional"))
    )
    (net (code "44") (name "POT2") (class "Default")
      (node (ref "POT_GPIO") (pin "2") (pinfunction "2_2") (pintype "passive"))
      (node (ref "SEED") (pin "29") (pinfunction "GPIO23(DAC1_OUT2)_29") (pintype "bidirectional"))
    )
    (net (code "45") (name "POT3") (class "Default")
      (node (ref "POT_GPIO") (pin "3") (pinfunction "3_3") (pintype "passive"))
      (node (ref "SEED") (pin "28") (pinfunction "GPIO22(ADC1_INP4)_28") (pintype "bidirectional"))
    )
    (net (code "46") (name "POT4") (class "Default")
      (node (ref "POT_GPIO") (pin "4") (pinfunction "4_4") (pintype "passive"))
      (node (ref "SEED") (pin "27") (pinfunction "GPIO21(ADC1_INP11)_27") (pintype "bidirectional"))
    )
    (net (code "47") (name "SPDT1_1") (class "Default")
      (node (ref "R22") (pin "P$2") (pinfunction "2_P$2") (pintype "passive"))
      (node (ref "SEED") (pin "11") (pinfunction "GPIO11(SPI1_MOSI)_11") (pintype "bidirectional"))
      (node (ref "SPDT_GPIO") (pin "4") (pinfunction "4_4") (pintype "passive"))
    )
    (net (code "48") (name "SPDT1_2") (class "Default")
      (node (ref "R21") (pin "P$2") (pinfunction "2_P$2") (pintype "passive"))
      (node (ref "SEED") (pin "12") (pinfunction "GPIO12(I2C1_SCL)_12") (pintype "bidirectional"))
      (node (ref "SPDT_GPIO") (pin "3") (pinfunction "3_3") (pintype "passive"))
    )
    (net (code "49") (name "SPDT2_1") (class "Default")
      (node (ref "R20") (pin "P$2") (pinfunction "2_P$2") (pintype "passive"))
      (node (ref "SEED") (pin "13") (pinfunction "GPIO13(I2C1_SDA)_13") (pintype "bidirectional"))
      (node (ref "SPDT_GPIO") (pin "2") (pinfunction "2_2") (pintype "passive"))
    )
    (net (code "50") (name "SPDT2_2") (class "Default")
      (node (ref "R19") (pin "P$2") (pinfunction "2_P$2") (pintype "passive"))
      (node (ref "SEED") (pin "14") (pinfunction "GPIO14(USART1_TX)_14") (pintype "bidirectional"))
      (node (ref "SPDT_GPIO") (pin "1") (pinfunction "1_1") (pintype "passive"))
    )
    (net (code "51") (name "SPST1") (class "Default")
      (node (ref "R18") (pin "P$2") (pinfunction "2_P$2") (pintype "passive"))
      (node (ref "SEED") (pin "6") (pinfunction "GPIO6(SDMMC1_CMD)_6") (pintype "bidirectional"))
      (node (ref "SPST_GPIO") (pin "4") (pinfunction "4_4") (pintype "passive"))
    )
    (net (code "52") (name "SPST2") (class "Default")
      (node (ref "R17") (pin "P$2") (pinfunction "2_P$2") (pintype "passive"))
      (node (ref "SEED") (pin "7") (pinfunction "GPIO7(SDMMC1_CK)_7") (pintype "bidirectional"))
      (node (ref "SPST_GPIO") (pin "3") (pinfunction "3_3") (pintype "passive"))
    )
    (net (code "53") (name "SPST3") (class "Default")
      (node (ref "R16") (pin "P$2") (pinfunction "2_P$2") (pintype "passive"))
      (node (ref "SEED") (pin "8") (pinfunction "GPIO8(SPI1_NSS)_8") (pintype "bidirectional"))
      (node (ref "SPST_GPIO") (pin "2") (pinfunction "2_2") (pintype "passive"))
    )
    (net (code "54") (name "SPST4") (class "Default")
      (node (ref "R15") (pin "P$2") (pinfunction "2_P$2") (pintype "passive"))
      (node (ref "SEED") (pin "9") (pinfunction "GPIO9(SPI1_SCK)_9") (pintype "bidirectional"))
      (node (ref "SPST_GPIO") (pin "1") (pinfunction "1_1") (pintype "passive"))
    )
    (net (code "55") (name "V_AUDIOBIAS") (class "Default")
      (node (ref "IC2") (pin "1") (pinfunction "OUT_1") (pintype "output"))
      (node (ref "IC2") (pin "2") (pinfunction "-IN_2") (pintype "input"))
      (node (ref "R3") (pin "P$2") (pinfunction "2_P$2") (pintype "passive"))
      (node (ref "R5") (pin "P$2") (pinfunction "2_P$2") (pintype "passive"))
    )
    (net (code "56") (name "unconnected-(SEED-GPIO5(SDMMC1_D0)-Pad5)") (class "Default")
      (node (ref "SEED") (pin "5") (pinfunction "GPIO5(SDMMC1_D0)_5") (pintype "bidirectional"))
    )
    (net (code "57") (name "unconnected-(SEED-GPIO10(SPI1_MISO)-Pad10)") (class "Default")
      (node (ref "SEED") (pin "10") (pinfunction "GPIO10(SPI1_MISO)_10") (pintype "bidirectional"))
    )
    (net (code "58") (name "unconnected-(SEED-GPIO15(USART1_RX)-Pad15)") (class "Default")
      (node (ref "SEED") (pin "15") (pinfunction "GPIO15(USART1_RX)_15") (pintype "bidirectional"))
    )
    (net (code "59") (name "unconnected-(SEED-GPIO20(ADC1_INP3)-Pad26)") (class "Default")
      (node (ref "SEED") (pin "26") (pinfunction "GPIO20(ADC1_INP3)_26") (pintype "bidirectional"))
    )
    (net (code "60") (name "unconnected-(SEED-GPIO25(SAI2_MCLK_B)-Pad31)") (class "Default")
      (node (ref "SEED") (pin "31") (pinfunction "GPIO25(SAI2_MCLK_B)_31") (pintype "bidirectional"))
    )
    (net (code "61") (name "unconnected-(SEED-GPIO26(SAI2_SD_B)-Pad32)") (class "Default")
      (node (ref "SEED") (pin "32") (pinfunction "GPIO26(SAI2_SD_B)_32") (pintype "bidirectional"))
    )
    (net (code "62") (name "unconnected-(SEED-GPIO31(USB_HS_D+)-Pad37)") (class "Default")
      (node (ref "SEED") (pin "37") (pinfunction "GPIO31(USB_HS_D+)_37") (pintype "bidirectional"))
    )
  )
)
